# BLE_Module.net
KiCad netlist of a schematic drawn in Altium Designer
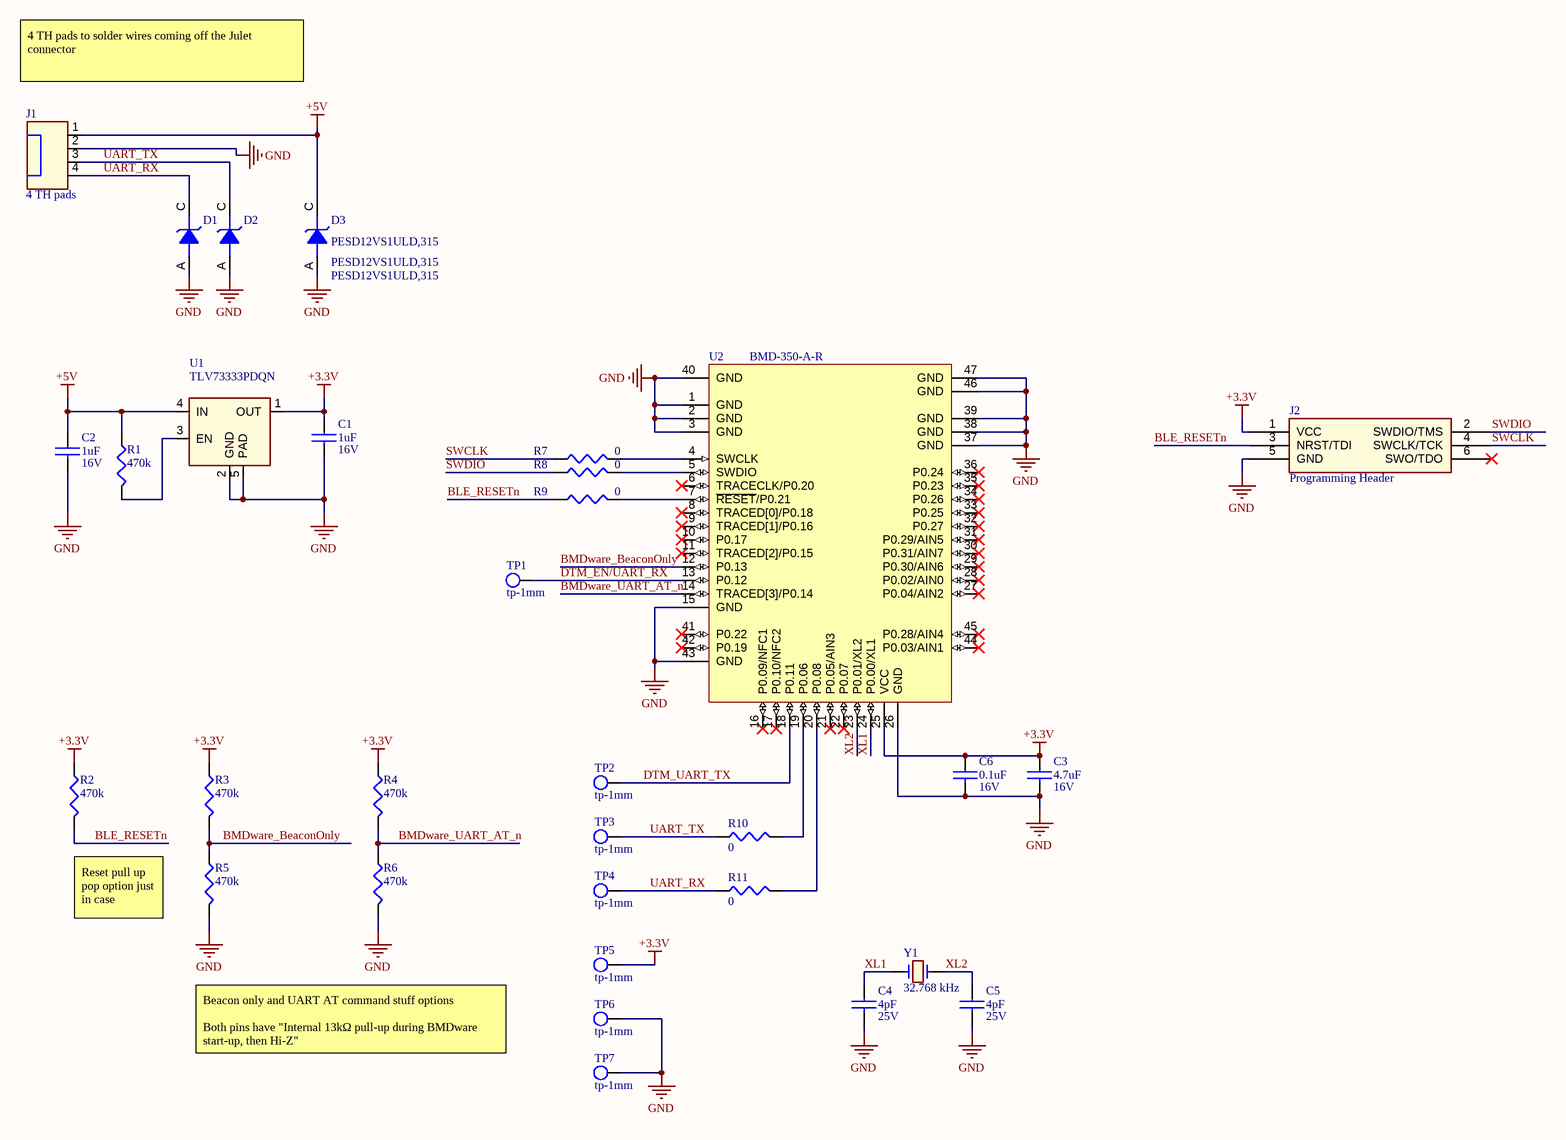
[diagram p0: BLE Module.SchDoc]

(export (version "E")
  (design (tool "Eeschema 10.0.6"))
  (components
    (comp (ref "C1")
      (value "1uF")
      (footprint "0603-ipcsm_90")
      (description "CAP CER 1UF 16V X7R 0603")
      (fields (field (name "VOLTAGE") "16V") (field (name "MFG") "Samsung") (field (name "TOLERANCE") "20%"))
      (libsource (lib "SynapseLibrary") (part "CAP"))
    )
    (comp (ref "C2")
      (value "1uF")
      (footprint "0603-ipcsm_90")
      (description "CAP CER 1UF 16V X7R 0603")
      (fields (field (name "VOLTAGE") "16V") (field (name "MFG") "Samsung") (field (name "TOLERANCE") "20%"))
      (libsource (lib "SynapseLibrary") (part "CAP"))
    )
    (comp (ref "C3")
      (value "4.7uF")
      (footprint "0603-ipcsm_90")
      (description "CAP CER 4.7UF 16V X5R 0603")
      (fields (field (name "VOLTAGE") "16V") (field (name "MFG") "Murata") (field (name "TOLERANCE") "10%"))
      (libsource (lib "SynapseLibrary") (part "CAP"))
    )
    (comp (ref "C4")
      (value "4pF")
      (footprint "0201-ipcsm_33")
      (description "CAP CER 4PF 50V C0G/NP0 0201")
      (fields (field (name "VOLTAGE") "25V") (field (name "MFG") "Murata") (field (name "TOLERANCE") "2.5%"))
      (libsource (lib "SynapseLibrary") (part "CAP"))
    )
    (comp (ref "C5")
      (value "4pF")
      (footprint "0201-ipcsm_33")
      (description "CAP CER 4PF 50V C0G/NP0 0201")
      (fields (field (name "VOLTAGE") "25V") (field (name "MFG") "Murata") (field (name "TOLERANCE") "2.5%"))
      (libsource (lib "SynapseLibrary") (part "CAP"))
    )
    (comp (ref "C6")
      (value "0.1uF")
      (footprint "0402-ipcsm_55")
      (description "CAP CER .1UF 16V X7R 0402")
      (fields (field (name "VOLTAGE") "16V") (field (name "MFG") "Murata") (field (name "TOLERANCE") "10%"))
      (libsource (lib "SynapseLibrary") (part "CAP"))
    )
    (comp (ref "D1")
      (value "PESD12VS1ULD,315")
      (footprint "SOD882D")
      (description "TVS DIODE 12V 35V 2DFN1006D")
      (fields (field (name "MFG") "Nexperia USA Inc."))
      (libsource (lib "SynapseLibrary") (part "TVS_UNI"))
    )
    (comp (ref "D2")
      (value "PESD12VS1ULD,315")
      (footprint "SOD882D")
      (description "TVS DIODE 12V 35V 2DFN1006D")
      (fields (field (name "MFG") "Nexperia USA Inc."))
      (libsource (lib "SynapseLibrary") (part "TVS_UNI"))
    )
    (comp (ref "D3")
      (value "PESD12VS1ULD,315")
      (footprint "SOD882D")
      (description "TVS DIODE 12V 35V 2DFN1006D")
      (fields (field (name "MFG") "Nexperia USA Inc."))
      (libsource (lib "SynapseLibrary") (part "TVS_UNI"))
    )
    (comp (ref "J1")
      (value "4 TH pads")
      (footprint "HEADER_1X4")
      (description "55 mm ZEBRA STRIP")
      (libsource (lib "SynapseLibrary") (part "HEADER 4"))
    )
    (comp (ref "J2")
      (value "Programming Header")
      (footprint "TC2030-MCP")
      (description "FOOTPRINT for CBL PLUG-OF-NAILS 6-PIN WITH CLIP")
      (libsource (lib "SynapseLibrary") (part "TC2030-IDC-NL"))
    )
    (comp (ref "R1")
      (value "470k")
      (footprint "0402-ipcsm_40")
      (description "RES 470K OHM 1/16W 1% 0402 SMD")
      (fields (field (name "MFG") "Panasonic") (field (name "TOLERANCE") "1%"))
      (libsource (lib "SynapseLibrary") (part "RES"))
    )
    (comp (ref "R2")
      (value "470k")
      (footprint "0402-ipcsm_40")
      (description "RES 470K OHM 1/16W 1% 0402 SMD")
      (fields (field (name "MFG") "Panasonic") (field (name "TOLERANCE") "1%"))
      (libsource (lib "SynapseLibrary") (part "RES"))
    )
    (comp (ref "R3")
      (value "470k")
      (footprint "0402-ipcsm_40")
      (description "RES 470K OHM 1/16W 1% 0402 SMD")
      (fields (field (name "MFG") "Panasonic") (field (name "TOLERANCE") "1%"))
      (libsource (lib "SynapseLibrary") (part "RES"))
    )
    (comp (ref "R4")
      (value "470k")
      (footprint "0402-ipcsm_40")
      (description "RES 470K OHM 1/16W 1% 0402 SMD")
      (fields (field (name "MFG") "Panasonic") (field (name "TOLERANCE") "1%"))
      (libsource (lib "SynapseLibrary") (part "RES"))
    )
    (comp (ref "R5")
      (value "470k")
      (footprint "0402-ipcsm_40")
      (description "RES 470K OHM 1/16W 1% 0402 SMD")
      (fields (field (name "MFG") "Panasonic") (field (name "TOLERANCE") "1%"))
      (libsource (lib "SynapseLibrary") (part "RES"))
    )
    (comp (ref "R6")
      (value "470k")
      (footprint "0402-ipcsm_40")
      (description "RES 470K OHM 1/16W 1% 0402 SMD")
      (fields (field (name "MFG") "Panasonic") (field (name "TOLERANCE") "1%"))
      (libsource (lib "SynapseLibrary") (part "RES"))
    )
    (comp (ref "R7")
      (value "0")
      (footprint "0402-ipcsm_40")
      (description "RES 0.0 OHM 1/10W JUMP 0402 SMD")
      (fields (field (name "MFG") "Panasonic") (field (name "TOLERANCE") "0%"))
      (libsource (lib "SynapseLibrary") (part "RES"))
    )
    (comp (ref "R8")
      (value "0")
      (footprint "0402-ipcsm_40")
      (description "RES 0.0 OHM 1/10W JUMP 0402 SMD")
      (fields (field (name "MFG") "Panasonic") (field (name "TOLERANCE") "0%"))
      (libsource (lib "SynapseLibrary") (part "RES"))
    )
    (comp (ref "R9")
      (value "0")
      (footprint "0402-ipcsm_40")
      (description "RES 0.0 OHM 1/10W JUMP 0402 SMD")
      (fields (field (name "MFG") "Panasonic") (field (name "TOLERANCE") "0%"))
      (libsource (lib "SynapseLibrary") (part "RES"))
    )
    (comp (ref "R10")
      (value "0")
      (footprint "0402-ipcsm_40")
      (description "RES 0.0 OHM 1/10W JUMP 0402 SMD")
      (fields (field (name "MFG") "Panasonic") (field (name "TOLERANCE") "0%"))
      (libsource (lib "SynapseLibrary") (part "RES"))
    )
    (comp (ref "R11")
      (value "0")
      (footprint "0402-ipcsm_40")
      (description "RES 0.0 OHM 1/10W JUMP 0402 SMD")
      (fields (field (name "MFG") "Panasonic") (field (name "TOLERANCE") "0%"))
      (libsource (lib "SynapseLibrary") (part "RES"))
    )
    (comp (ref "TP1")
      (value "tp-1mm")
      (footprint "tp-1mm")
      (description "TESTPOINT, 1MM SMD")
      (libsource (lib "SynapseLibrary") (part "tp_smt"))
    )
    (comp (ref "TP2")
      (value "tp-1mm")
      (footprint "tp-1mm")
      (description "TESTPOINT, 1MM SMD")
      (libsource (lib "SynapseLibrary") (part "tp_smt"))
    )
    (comp (ref "TP3")
      (value "tp-1mm")
      (footprint "tp-1mm")
      (description "TESTPOINT, 1MM SMD")
      (libsource (lib "SynapseLibrary") (part "tp_smt"))
    )
    (comp (ref "TP4")
      (value "tp-1mm")
      (footprint "tp-1mm")
      (description "TESTPOINT, 1MM SMD")
      (libsource (lib "SynapseLibrary") (part "tp_smt"))
    )
    (comp (ref "TP5")
      (value "tp-1mm")
      (footprint "tp-1mm")
      (description "TESTPOINT, 1MM SMD")
      (libsource (lib "SynapseLibrary") (part "tp_smt"))
    )
    (comp (ref "TP6")
      (value "tp-1mm")
      (footprint "tp-1mm")
      (description "TESTPOINT, 1MM SMD")
      (libsource (lib "SynapseLibrary") (part "tp_smt"))
    )
    (comp (ref "TP7")
      (value "tp-1mm")
      (footprint "tp-1mm")
      (description "TESTPOINT, 1MM SMD")
      (libsource (lib "SynapseLibrary") (part "tp_smt"))
    )
    (comp (ref "U1")
      (value "TLV73333PDQN")
      (footprint "son4_tlv707dqn")
      (description "IC REG LINEAR 3.3V 300MA 4X2SON")
      (fields (field (name "MFG") "Texas Instruments"))
      (libsource (lib "SynapseLibrary") (part "TLV707XX"))
    )
    (comp (ref "U2")
      (value "BMD-350-A-R")
      (footprint "BMD-350")
      (description "MOD BLE 4.2 NORDIC NRF52832 SOC")
      (fields
        (field (name "MANUFACTURER") "Rigado")
        (field (name "PART NUMBER") "BMD-350-A")
        (field (name "ADDED BY") "Cam N")
      )
      (libsource (lib "SynapseLibrary") (part "BMD-350"))
    )
    (comp (ref "Y1")
      (value "32.768 kHz")
      (footprint "xtal_ABS07-120")
      (description "CRYSTAL 32.768KHZ 6PF SMD")
      (fields (field (name "MFG") "Abracon"))
      (libsource (lib "SynapseLibrary") (part "XTAL_32K"))
    )
  )
  (nets
    (net (code "1") (name "+3.3V") (class "Default")
      (node (ref "C1") (pin "1") (pinfunction "1_1") (pintype "passive"))
      (node (ref "C3") (pin "1") (pinfunction "1_1") (pintype "passive"))
      (node (ref "C6") (pin "1") (pinfunction "1_1") (pintype "passive"))
      (node (ref "J2") (pin "1") (pinfunction "VCC_1") (pintype "passive"))
      (node (ref "R2") (pin "1") (pinfunction "1_1") (pintype "passive"))
      (node (ref "R3") (pin "1") (pinfunction "1_1") (pintype "passive"))
      (node (ref "R4") (pin "1") (pinfunction "1_1") (pintype "passive"))
      (node (ref "TP5") (pin "1") (pinfunction "TP_1") (pintype "passive"))
      (node (ref "U1") (pin "1") (pinfunction "OUT_1") (pintype "passive"))
      (node (ref "U2") (pin "25") (pinfunction "VCC_25") (pintype "power_in"))
    )
    (net (code "2") (name "+5V") (class "Default")
      (node (ref "C2") (pin "1") (pinfunction "1_1") (pintype "passive"))
      (node (ref "D3") (pin "C") (pinfunction "C_C") (pintype "passive"))
      (node (ref "J1") (pin "1") (pinfunction "1_1") (pintype "passive"))
      (node (ref "R1") (pin "1") (pinfunction "1_1") (pintype "passive"))
      (node (ref "U1") (pin "4") (pinfunction "IN_4") (pintype "passive"))
    )
    (net (code "3") (name "/BLE_RESETn") (class "Default")
      (node (ref "J2") (pin "3") (pinfunction "NRST/TDI_3") (pintype "passive"))
      (node (ref "R2") (pin "2") (pinfunction "2_2") (pintype "passive"))
      (node (ref "R9") (pin "1") (pinfunction "1_1") (pintype "passive"))
    )
    (net (code "4") (name "/BMDware_BeaconOnly") (class "Default")
      (node (ref "R3") (pin "2") (pinfunction "2_2") (pintype "passive"))
      (node (ref "R5") (pin "1") (pinfunction "1_1") (pintype "passive"))
      (node (ref "U2") (pin "12") (pinfunction "P0.13_12") (pintype "bidirectional"))
    )
    (net (code "5") (name "/BMDware_UART_AT_n") (class "Default")
      (node (ref "R4") (pin "2") (pinfunction "2_2") (pintype "passive"))
      (node (ref "R6") (pin "1") (pinfunction "1_1") (pintype "passive"))
      (node (ref "U2") (pin "14") (pinfunction "TRACED[3]/P0.14_14") (pintype "bidirectional"))
    )
    (net (code "6") (name "/DTM_EN{slash}UART_RX") (class "Default")
      (node (ref "TP1") (pin "1") (pinfunction "TP_1") (pintype "passive"))
      (node (ref "U2") (pin "13") (pinfunction "P0.12_13") (pintype "bidirectional"))
    )
    (net (code "7") (name "/DTM_UART_TX") (class "Default")
      (node (ref "TP2") (pin "1") (pinfunction "TP_1") (pintype "passive"))
      (node (ref "U2") (pin "18") (pinfunction "P0.11_18") (pintype "bidirectional"))
    )
    (net (code "8") (name "/SWCLK") (class "Default")
      (node (ref "J2") (pin "4") (pinfunction "SWCLK/TCK_4") (pintype "passive"))
      (node (ref "R7") (pin "1") (pinfunction "1_1") (pintype "passive"))
    )
    (net (code "9") (name "/SWDIO") (class "Default")
      (node (ref "J2") (pin "2") (pinfunction "SWDIO/TMS_2") (pintype "passive"))
      (node (ref "R8") (pin "1") (pinfunction "1_1") (pintype "passive"))
    )
    (net (code "10") (name "/UART_RX") (class "Default")
      (node (ref "D1") (pin "C") (pinfunction "C_C") (pintype "passive"))
      (node (ref "J1") (pin "4") (pinfunction "4_4") (pintype "passive"))
      (node (ref "R11") (pin "1") (pinfunction "1_1") (pintype "passive"))
      (node (ref "TP4") (pin "1") (pinfunction "TP_1") (pintype "passive"))
    )
    (net (code "11") (name "/UART_TX") (class "Default")
      (node (ref "D2") (pin "C") (pinfunction "C_C") (pintype "passive"))
      (node (ref "J1") (pin "3") (pinfunction "3_3") (pintype "passive"))
      (node (ref "R10") (pin "1") (pinfunction "1_1") (pintype "passive"))
      (node (ref "TP3") (pin "1") (pinfunction "TP_1") (pintype "passive"))
    )
    (net (code "12") (name "/XL1") (class "Default")
      (node (ref "C4") (pin "1") (pinfunction "1_1") (pintype "passive"))
      (node (ref "U2") (pin "24") (pinfunction "P0.00/XL1_24") (pintype "bidirectional"))
      (node (ref "Y1") (pin "1") (pinfunction "1_1") (pintype "passive"))
    )
    (net (code "13") (name "/XL2") (class "Default")
      (node (ref "C5") (pin "1") (pinfunction "1_1") (pintype "passive"))
      (node (ref "U2") (pin "23") (pinfunction "P0.01/XL2_23") (pintype "bidirectional"))
      (node (ref "Y1") (pin "2") (pinfunction "2_2") (pintype "passive"))
    )
    (net (code "14") (name "GND") (class "Default")
      (node (ref "C1") (pin "2") (pinfunction "2_2") (pintype "passive"))
      (node (ref "C2") (pin "2") (pinfunction "2_2") (pintype "passive"))
      (node (ref "C3") (pin "2") (pinfunction "2_2") (pintype "passive"))
      (node (ref "C4") (pin "2") (pinfunction "2_2") (pintype "passive"))
      (node (ref "C5") (pin "2") (pinfunction "2_2") (pintype "passive"))
      (node (ref "C6") (pin "2") (pinfunction "2_2") (pintype "passive"))
      (node (ref "D1") (pin "A") (pinfunction "A_A") (pintype "passive"))
      (node (ref "D2") (pin "A") (pinfunction "A_A") (pintype "passive"))
      (node (ref "D3") (pin "A") (pinfunction "A_A") (pintype "passive"))
      (node (ref "J1") (pin "2") (pinfunction "2_2") (pintype "passive"))
      (node (ref "J2") (pin "5") (pinfunction "GND_5") (pintype "passive"))
      (node (ref "R5") (pin "2") (pinfunction "2_2") (pintype "passive"))
      (node (ref "R6") (pin "2") (pinfunction "2_2") (pintype "passive"))
      (node (ref "TP6") (pin "1") (pinfunction "TP_1") (pintype "passive"))
      (node (ref "TP7") (pin "1") (pinfunction "TP_1") (pintype "passive"))
      (node (ref "U1") (pin "2") (pinfunction "GND_2") (pintype "passive"))
      (node (ref "U1") (pin "5") (pinfunction "PAD_5") (pintype "passive"))
      (node (ref "U2") (pin "1") (pinfunction "GND_1") (pintype "power_in"))
      (node (ref "U2") (pin "15") (pinfunction "GND_15") (pintype "power_in"))
      (node (ref "U2") (pin "2") (pinfunction "GND_2") (pintype "power_in"))
      (node (ref "U2") (pin "26") (pinfunction "GND_26") (pintype "power_in"))
      (node (ref "U2") (pin "3") (pinfunction "GND_3") (pintype "power_in"))
      (node (ref "U2") (pin "37") (pinfunction "GND_37") (pintype "power_in"))
      (node (ref "U2") (pin "38") (pinfunction "GND_38") (pintype "power_in"))
      (node (ref "U2") (pin "39") (pinfunction "GND_39") (pintype "power_in"))
      (node (ref "U2") (pin "40") (pinfunction "GND_40") (pintype "power_in"))
      (node (ref "U2") (pin "43") (pinfunction "GND_43") (pintype "power_in"))
      (node (ref "U2") (pin "46") (pinfunction "GND_46") (pintype "power_in"))
      (node (ref "U2") (pin "47") (pinfunction "GND_47") (pintype "power_in"))
    )
    (net (code "15") (name "Net-(U1-EN)") (class "Default")
      (node (ref "R1") (pin "2") (pinfunction "2_2") (pintype "passive"))
      (node (ref "U1") (pin "3") (pinfunction "EN_3") (pintype "passive"))
    )
    (net (code "16") (name "Net-(U2-P0.06)") (class "Default")
      (node (ref "R10") (pin "2") (pinfunction "2_2") (pintype "passive"))
      (node (ref "U2") (pin "19") (pinfunction "P0.06_19") (pintype "bidirectional"))
    )
    (net (code "17") (name "Net-(U2-P0.08)") (class "Default")
      (node (ref "R11") (pin "2") (pinfunction "2_2") (pintype "passive"))
      (node (ref "U2") (pin "20") (pinfunction "P0.08_20") (pintype "bidirectional"))
    )
    (net (code "18") (name "Net-(U2-SWCLK)") (class "Default")
      (node (ref "R7") (pin "2") (pinfunction "2_2") (pintype "passive"))
      (node (ref "U2") (pin "4") (pinfunction "SWCLK_4") (pintype "input"))
    )
    (net (code "19") (name "Net-(U2-SWDIO)") (class "Default")
      (node (ref "R8") (pin "2") (pinfunction "2_2") (pintype "passive"))
      (node (ref "U2") (pin "5") (pinfunction "SWDIO_5") (pintype "bidirectional"))
    )
    (net (code "20") (name "Net-(U2-~{RESET}{slash}P0.21)") (class "Default")
      (node (ref "R9") (pin "2") (pinfunction "2_2") (pintype "passive"))
      (node (ref "U2") (pin "7") (pinfunction "~{RESET}/P0.21_7") (pintype "bidirectional"))
    )
    (net (code "21") (name "unconnected-(J2-SWO{slash}TDO-Pad6)") (class "Default")
      (node (ref "J2") (pin "6") (pinfunction "SWO/TDO_6") (pintype "passive+no_connect"))
    )
    (net (code "22") (name "unconnected-(U2-P0.02{slash}AIN0-Pad28)") (class "Default")
      (node (ref "U2") (pin "28") (pinfunction "P0.02/AIN0_28") (pintype "bidirectional+no_connect"))
    )
    (net (code "23") (name "unconnected-(U2-P0.03{slash}AIN1-Pad44)") (class "Default")
      (node (ref "U2") (pin "44") (pinfunction "P0.03/AIN1_44") (pintype "bidirectional+no_connect"))
    )
    (net (code "24") (name "unconnected-(U2-P0.04{slash}AIN2-Pad27)") (class "Default")
      (node (ref "U2") (pin "27") (pinfunction "P0.04/AIN2_27") (pintype "bidirectional+no_connect"))
    )
    (net (code "25") (name "unconnected-(U2-P0.05{slash}AIN3-Pad21)") (class "Default")
      (node (ref "U2") (pin "21") (pinfunction "P0.05/AIN3_21") (pintype "bidirectional+no_connect"))
    )
    (net (code "26") (name "unconnected-(U2-P0.07-Pad22)") (class "Default")
      (node (ref "U2") (pin "22") (pinfunction "P0.07_22") (pintype "bidirectional+no_connect"))
    )
    (net (code "27") (name "unconnected-(U2-P0.09{slash}NFC1-Pad16)") (class "Default")
      (node (ref "U2") (pin "16") (pinfunction "P0.09/NFC1_16") (pintype "bidirectional+no_connect"))
    )
    (net (code "28") (name "unconnected-(U2-P0.10{slash}NFC2-Pad17)") (class "Default")
      (node (ref "U2") (pin "17") (pinfunction "P0.10/NFC2_17") (pintype "bidirectional+no_connect"))
    )
    (net (code "29") (name "unconnected-(U2-P0.17-Pad10)") (class "Default")
      (node (ref "U2") (pin "10") (pinfunction "P0.17_10") (pintype "bidirectional+no_connect"))
    )
    (net (code "30") (name "unconnected-(U2-P0.19-Pad42)") (class "Default")
      (node (ref "U2") (pin "42") (pinfunction "P0.19_42") (pintype "bidirectional+no_connect"))
    )
    (net (code "31") (name "unconnected-(U2-P0.22-Pad41)") (class "Default")
      (node (ref "U2") (pin "41") (pinfunction "P0.22_41") (pintype "bidirectional+no_connect"))
    )
    (net (code "32") (name "unconnected-(U2-P0.23-Pad35)") (class "Default")
      (node (ref "U2") (pin "35") (pinfunction "P0.23_35") (pintype "bidirectional+no_connect"))
    )
    (net (code "33") (name "unconnected-(U2-P0.24-Pad36)") (class "Default")
      (node (ref "U2") (pin "36") (pinfunction "P0.24_36") (pintype "bidirectional+no_connect"))
    )
    (net (code "34") (name "unconnected-(U2-P0.25-Pad33)") (class "Default")
      (node (ref "U2") (pin "33") (pinfunction "P0.25_33") (pintype "bidirectional+no_connect"))
    )
    (net (code "35") (name "unconnected-(U2-P0.26-Pad34)") (class "Default")
      (node (ref "U2") (pin "34") (pinfunction "P0.26_34") (pintype "bidirectional+no_connect"))
    )
    (net (code "36") (name "unconnected-(U2-P0.27-Pad32)") (class "Default")
      (node (ref "U2") (pin "32") (pinfunction "P0.27_32") (pintype "bidirectional+no_connect"))
    )
    (net (code "37") (name "unconnected-(U2-P0.28{slash}AIN4-Pad45)") (class "Default")
      (node (ref "U2") (pin "45") (pinfunction "P0.28/AIN4_45") (pintype "bidirectional+no_connect"))
    )
    (net (code "38") (name "unconnected-(U2-P0.29{slash}AIN5-Pad31)") (class "Default")
      (node (ref "U2") (pin "31") (pinfunction "P0.29/AIN5_31") (pintype "bidirectional+no_connect"))
    )
    (net (code "39") (name "unconnected-(U2-P0.30{slash}AIN6-Pad29)") (class "Default")
      (node (ref "U2") (pin "29") (pinfunction "P0.30/AIN6_29") (pintype "bidirectional+no_connect"))
    )
    (net (code "40") (name "unconnected-(U2-P0.31{slash}AIN7-Pad30)") (class "Default")
      (node (ref "U2") (pin "30") (pinfunction "P0.31/AIN7_30") (pintype "bidirectional+no_connect"))
    )
    (net (code "41") (name "unconnected-(U2-TRACECLK{slash}P0.20-Pad6)") (class "Default")
      (node (ref "U2") (pin "6") (pinfunction "TRACECLK/P0.20_6") (pintype "bidirectional+no_connect"))
    )
    (net (code "42") (name "unconnected-(U2-TRACED[0]{slash}P0.18-Pad8)") (class "Default")
      (node (ref "U2") (pin "8") (pinfunction "TRACED[0]/P0.18_8") (pintype "bidirectional+no_connect"))
    )
    (net (code "43") (name "unconnected-(U2-TRACED[1]{slash}P0.16-Pad9)") (class "Default")
      (node (ref "U2") (pin "9") (pinfunction "TRACED[1]/P0.16_9") (pintype "bidirectional+no_connect"))
    )
    (net (code "44") (name "unconnected-(U2-TRACED[2]{slash}P0.15-Pad11)") (class "Default")
      (node (ref "U2") (pin "11") (pinfunction "TRACED[2]/P0.15_11") (pintype "bidirectional+no_connect"))
    )
  )
)
